# Tape.net
KiCad netlist of a schematic drawn in Altium Designer
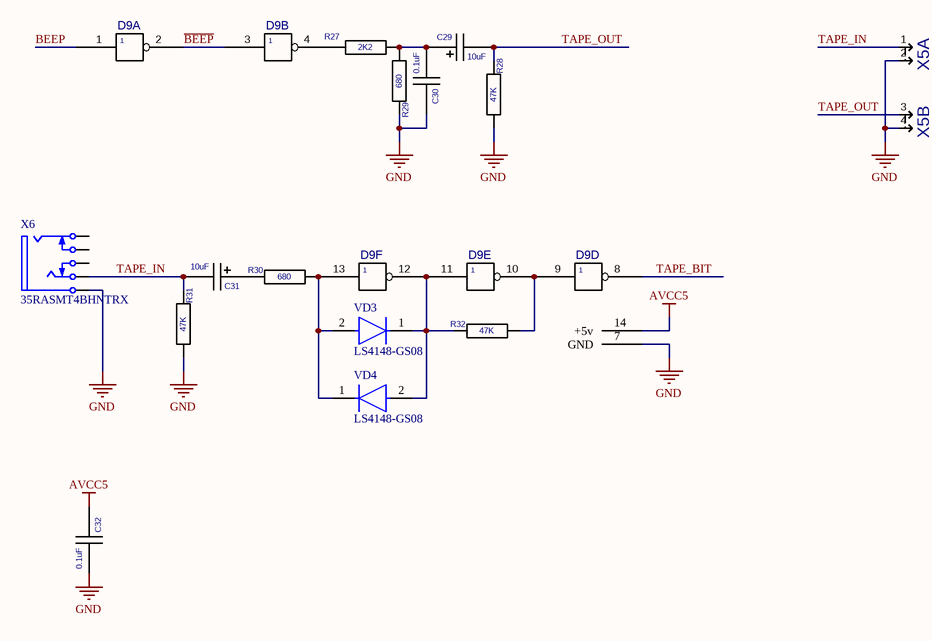
[diagram p0: Tape.SchDoc]

(export (version "E")
  (design (tool "Eeschema 10.0.6"))
  (components
    (comp (ref "C29")
      (value "10uF")
      (footprint "EC-CHIP")
      (description "ECAPCHIP")
      (libsource (lib "*") (part "ECAPCHIP"))
    )
    (comp (ref "C30")
      (value "0.1uF")
      (footprint "C-CHIP")
      (description "CAPCHIP")
      (libsource (lib "*") (part "CAPCHIP"))
    )
    (comp (ref "C31")
      (value "10uF")
      (footprint "EC-CHIP")
      (description "ECAPCHIP")
      (libsource (lib "*") (part "ECAPCHIP"))
    )
    (comp (ref "C32")
      (value "0.1uF")
      (footprint "C-CHIP")
      (description "CAPCHIP")
      (libsource (lib "*") (part "CAPCHIP"))
    )
    (comp (ref "D9") (value "CD4069M") (footprint "SO14") (libsource (lib "*") (part "CD4069M")))
    (comp (ref "R27")
      (value "2K2")
      (footprint "R-CHIP")
      (description "RESCHIP")
      (libsource (lib "*") (part "RESCHIP"))
    )
    (comp (ref "R28")
      (value "47K")
      (footprint "R-CHIP")
      (description "RESCHIP")
      (libsource (lib "*") (part "RESCHIP"))
    )
    (comp (ref "R29")
      (value "680")
      (footprint "R-CHIP")
      (description "RESCHIP")
      (libsource (lib "*") (part "RESCHIP"))
    )
    (comp (ref "R30")
      (value "680")
      (footprint "R-CHIP")
      (description "RESCHIP")
      (libsource (lib "*") (part "RESCHIP"))
    )
    (comp (ref "R31")
      (value "47K")
      (footprint "R-CHIP")
      (description "RESCHIP")
      (libsource (lib "*") (part "RESCHIP"))
    )
    (comp (ref "R32")
      (value "47K")
      (footprint "R-CHIP")
      (description "RESCHIP")
      (libsource (lib "*") (part "RESCHIP"))
    )
    (comp (ref "VD3")
      (value "LS4148-GS08")
      (footprint "FP-6_560-5006_01-4-MFG")
      (description "DIODE GEN PURP 75V 150MA SOD80")
      (fields
        (field (name "OCTOPART") "https://octopart.com/ls4148-gs08-vishay-55401771")
        (field (name "MANUFACTURER") "Vishay Semiconductor Diodes Division")
      )
      (libsource (lib "Altium Content Vault") (part "d7152d700b627762746794eb795d46e"))
    )
    (comp (ref "VD4")
      (value "LS4148-GS08")
      (footprint "FP-6_560-5006_01-4-MFG")
      (description "DIODE GEN PURP 75V 150MA SOD80")
      (fields
        (field (name "OCTOPART") "https://octopart.com/ls4148-gs08-vishay-55401771")
        (field (name "MANUFACTURER") "Vishay Semiconductor Diodes Division")
      )
      (libsource (lib "Altium Content Vault") (part "d7152d700b627762746794eb795d46e"))
    )
    (comp (ref "X5") (value "PLB2-2") (footprint "PLB2-2") (libsource (lib "*") (part "PLB2-2")))
    (comp (ref "X6")
      (value "35RASMT4BHNTRX")
      (footprint "SWIT-35RASMT4BHNTRX_V")
      (description "Female 3.5 mm Phone Jack, 5 Position, Height 5 mm, RoHS, Tape and Reel")
      (libsource (lib "Altium Content Vault") (part "JACK-3CD5-RN"))
    )
  )
  (nets
    (net (code "1") (name "+5v") (class "Default")
      (node (ref "D9") (pin "14") (pinfunction "+5v_14") (pintype "power_in"))
    )
    (net (code "2") (name "/BEEP") (class "Default") (node (ref "D9") (pin "1") (pintype "passive")))
    (net (code "3") (name "/TAPE_BIT") (class "Default") (node (ref "D9") (pin "8") (pintype "passive")))
    (net (code "4") (name "/TAPE_IN") (class "Default")
      (node (ref "C31") (pin "2") (pintype "passive"))
      (node (ref "R31") (pin "2") (pinfunction "i/o1_2") (pintype "passive"))
      (node (ref "X5") (pin "1") (pinfunction "1_1") (pintype "passive"))
      (node (ref "X6") (pin "3") (pinfunction "3_3") (pintype "passive"))
    )
    (net (code "5") (name "/TAPE_OUT") (class "Default")
      (node (ref "C29") (pin "2") (pintype "passive"))
      (node (ref "R28") (pin "2") (pinfunction "i/o1_2") (pintype "passive"))
      (node (ref "X5") (pin "3") (pinfunction "1_3") (pintype "passive"))
    )
    (net (code "6") (name "/~{BEEP}") (class "Default")
      (node (ref "D9") (pin "2") (pintype "passive"))
      (node (ref "D9") (pin "3") (pintype "passive"))
    )
    (net (code "7") (name "AVCC5") (class "Default")
      (node (ref "C32") (pin "1") (pinfunction "1_1") (pintype "passive"))
      (node (ref "D9") (pin "14") (pinfunction "+5v_14") (pintype "power_in"))
    )
    (net (code "8") (name "GND") (class "Default")
      (node (ref "C30") (pin "1") (pinfunction "1_1") (pintype "passive"))
      (node (ref "C32") (pin "2") (pinfunction "2_2") (pintype "passive"))
      (node (ref "D9") (pin "7") (pinfunction "GND_7") (pintype "power_in"))
      (node (ref "R28") (pin "1") (pinfunction "i/o_1") (pintype "passive"))
      (node (ref "R29") (pin "2") (pinfunction "i/o1_2") (pintype "passive"))
      (node (ref "R31") (pin "1") (pinfunction "i/o_1") (pintype "passive"))
      (node (ref "X5") (pin "2") (pinfunction "2_2") (pintype "passive"))
      (node (ref "X5") (pin "4") (pinfunction "2_4") (pintype "passive"))
      (node (ref "X6") (pin "1") (pinfunction "1_1") (pintype "passive"))
    )
    (net (code "9") (name "Net-(R27-i{slash}o)") (class "Default")
      (node (ref "C29") (pin "1") (pintype "passive"))
      (node (ref "C30") (pin "2") (pinfunction "2_2") (pintype "passive"))
      (node (ref "R27") (pin "1") (pinfunction "i/o_1") (pintype "passive"))
      (node (ref "R29") (pin "1") (pinfunction "i/o_1") (pintype "passive"))
    )
    (net (code "10") (name "Net-(R27-i{slash}o1)") (class "Default")
      (node (ref "D9") (pin "4") (pintype "passive"))
      (node (ref "R27") (pin "2") (pinfunction "i/o1_2") (pintype "passive"))
    )
    (net (code "11") (name "Net-(R30-i{slash}o)") (class "Default")
      (node (ref "D9") (pin "13") (pintype "passive"))
      (node (ref "R30") (pin "1") (pinfunction "i/o_1") (pintype "passive"))
      (node (ref "VD3") (pin "2") (pinfunction "A_2") (pintype "passive"))
      (node (ref "VD4") (pin "1") (pinfunction "C_1") (pintype "passive"))
    )
    (net (code "12") (name "Net-(R30-i{slash}o1)") (class "Default")
      (node (ref "C31") (pin "1") (pintype "passive"))
      (node (ref "R30") (pin "2") (pinfunction "i/o1_2") (pintype "passive"))
    )
    (net (code "13") (name "Net-(R32-i{slash}o)") (class "Default")
      (node (ref "D9") (pin "10") (pintype "passive"))
      (node (ref "D9") (pin "9") (pintype "passive"))
      (node (ref "R32") (pin "1") (pinfunction "i/o_1") (pintype "passive"))
    )
    (net (code "14") (name "Net-(R32-i{slash}o1)") (class "Default")
      (node (ref "D9") (pin "11") (pintype "passive"))
      (node (ref "D9") (pin "12") (pintype "passive"))
      (node (ref "R32") (pin "2") (pinfunction "i/o1_2") (pintype "passive"))
      (node (ref "VD3") (pin "1") (pinfunction "C_1") (pintype "passive"))
      (node (ref "VD4") (pin "2") (pinfunction "A_2") (pintype "passive"))
    )
    (net (code "15") (name "unconnected-(X6-Pad2)") (class "Default")
      (node (ref "X6") (pin "2") (pinfunction "2_2") (pintype "passive"))
    )
    (net (code "16") (name "unconnected-(X6-Pad4)") (class "Default")
      (node (ref "X6") (pin "4") (pinfunction "4_4") (pintype "passive"))
    )
    (net (code "17") (name "unconnected-(X6-Pad5)") (class "Default")
      (node (ref "X6") (pin "5") (pinfunction "5_5") (pintype "passive"))
    )
  )
)
